# TDA7052AT_BRK.net
KiCad netlist of a schematic drawn in EAGLE
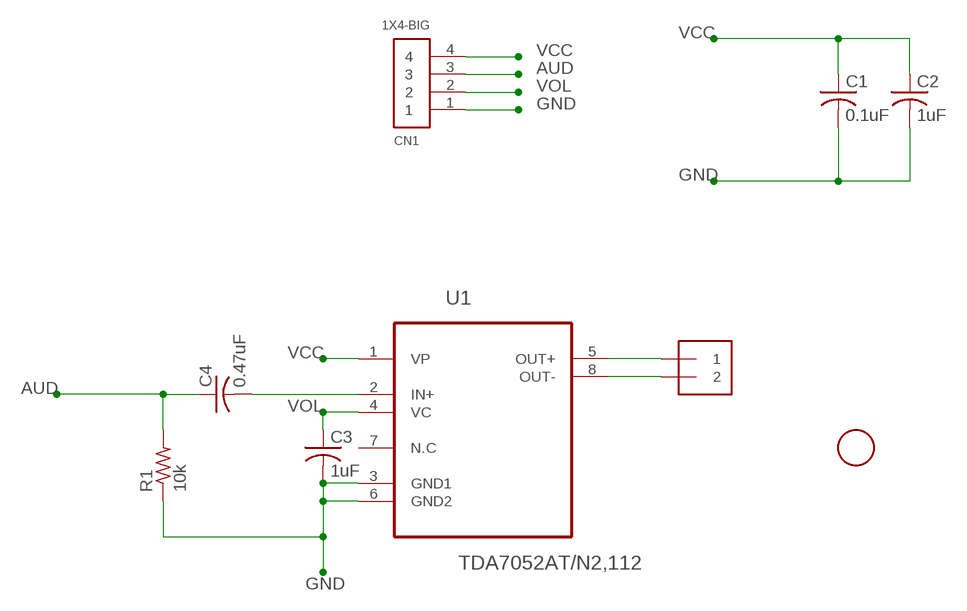
[diagram p0: schematic, sheet 1]

(export (version "E")
  (design (tool "Eeschema 10.0.6"))
  (components
    (comp (ref "C1")
      (value "0.1uF")
      (footprint "eagle-import:C0603K")
      (libsource (lib "eagle-import") (part "C-USC0603K"))
    )
    (comp (ref "C2")
      (value "1uF")
      (footprint "eagle-import:C0603K")
      (libsource (lib "eagle-import") (part "C-USC0603K"))
    )
    (comp (ref "C3")
      (value "1uF")
      (footprint "eagle-import:C0603K")
      (libsource (lib "eagle-import") (part "C-USC0603K"))
    )
    (comp (ref "C4")
      (value "0.47uF")
      (footprint "eagle-import:C0805K")
      (libsource (lib "eagle-import") (part "C-USC0805K"))
    )
    (comp (ref "CN1")
      (value "1X4-BIG")
      (footprint "eagle-import:1X04-BIG")
      (libsource (lib "eagle-import") (part "1X4-BIG"))
    )
    (comp (ref "J1")
      (value "1X2-3.5MM")
      (footprint "eagle-import:1X2-3.5MM")
      (libsource (lib "eagle-import") (part "1X2-3.5MM"))
    )
    (comp (ref "R1")
      (value "10k")
      (footprint "eagle-import:R0805")
      (libsource (lib "eagle-import") (part "R-US_R0805"))
    )
    (comp (ref "U$1")
      (value "FIDUCIAL")
      (footprint "eagle-import:FIDUCIAL_1MM")
      (libsource (lib "eagle-import") (part "FIDUCIAL"))
    )
    (comp (ref "U1")
      (value "TDA7052AT/N2,112")
      (footprint "eagle-import:SOIC127P600X175-8N")
      (libsource (lib "eagle-import") (part "TDA7052AT/N2,112"))
    )
  )
  (nets
    (net (code "1") (name "/AUD") (class "Default")
      (node (ref "C4") (pin "1") (pinfunction "1_1") (pintype "passive"))
      (node (ref "CN1") (pin "3") (pinfunction "3_3") (pintype "bidirectional"))
      (node (ref "R1") (pin "2") (pinfunction "2_2") (pintype "passive"))
    )
    (net (code "2") (name "/GND") (class "Default")
      (node (ref "C1") (pin "2") (pinfunction "2_2") (pintype "passive"))
      (node (ref "C2") (pin "2") (pinfunction "2_2") (pintype "passive"))
      (node (ref "C3") (pin "2") (pinfunction "2_2") (pintype "passive"))
      (node (ref "CN1") (pin "1") (pinfunction "1_1") (pintype "bidirectional"))
      (node (ref "R1") (pin "1") (pinfunction "1_1") (pintype "passive"))
      (node (ref "U1") (pin "3") (pinfunction "GND1_3") (pintype "passive"))
      (node (ref "U1") (pin "6") (pinfunction "GND2_6") (pintype "passive"))
    )
    (net (code "3") (name "/VCC") (class "Default")
      (node (ref "C1") (pin "1") (pinfunction "1_1") (pintype "passive"))
      (node (ref "C2") (pin "1") (pinfunction "1_1") (pintype "passive"))
      (node (ref "CN1") (pin "4") (pinfunction "4_4") (pintype "bidirectional"))
      (node (ref "U1") (pin "1") (pinfunction "VP_1") (pintype "power_in"))
    )
    (net (code "4") (name "/VOL") (class "Default")
      (node (ref "C3") (pin "1") (pinfunction "1_1") (pintype "passive"))
      (node (ref "CN1") (pin "2") (pinfunction "2_2") (pintype "bidirectional"))
      (node (ref "U1") (pin "4") (pinfunction "VC_4") (pintype "input"))
    )
    (net (code "5") (name "Net-(U1-IN+)") (class "Default")
      (node (ref "C4") (pin "2") (pinfunction "2_2") (pintype "passive"))
      (node (ref "U1") (pin "2") (pinfunction "IN+_2") (pintype "input"))
    )
    (net (code "6") (name "Net-(U1-OUT+)") (class "Default")
      (node (ref "J1") (pin "1") (pinfunction "1_1") (pintype "passive"))
      (node (ref "U1") (pin "5") (pinfunction "OUT+_5") (pintype "output"))
    )
    (net (code "7") (name "Net-(U1-OUT-)") (class "Default")
      (node (ref "J1") (pin "2") (pinfunction "2_2") (pintype "passive"))
      (node (ref "U1") (pin "8") (pinfunction "OUT-_8") (pintype "output"))
    )
    (net (code "8") (name "unconnected-(U1-N.C-Pad7)") (class "Default")
      (node (ref "U1") (pin "7") (pinfunction "N.C_7") (pintype "no_connect"))
    )
  )
)
